# triState.net
KiCad netlist of a schematic drawn in EAGLE
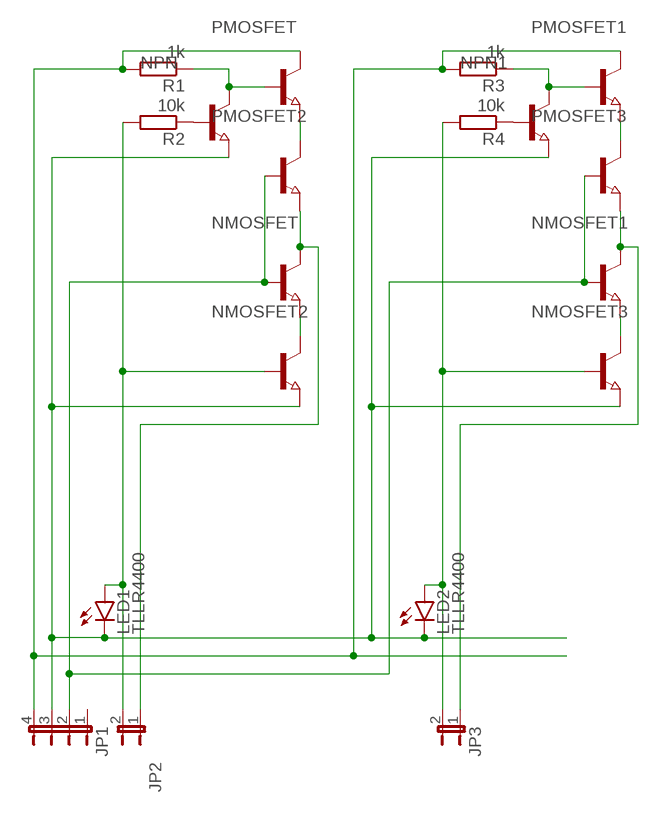
[diagram p0: schematic, sheet 1]

(export (version "E")
  (design (tool "Eeschema 10.0.6"))
  (components
    (comp (ref "JP1")
      (value "JP4E")
      (footprint "eagle-import:JP4")
      (libsource (lib "eagle-import") (part "JP4E"))
    )
    (comp (ref "JP2")
      (value "JP1E")
      (footprint "eagle-import:JP1")
      (libsource (lib "eagle-import") (part "JP1E"))
    )
    (comp (ref "JP3")
      (value "JP1E")
      (footprint "eagle-import:JP1")
      (libsource (lib "eagle-import") (part "JP1E"))
    )
    (comp (ref "LED1")
      (value "TLLR4400")
      (footprint "eagle-import:LED3MM")
      (fields (field (name "MF") "VISHAY SEMICONDUCTOR"))
      (libsource (lib "eagle-import") (part "TLLR4400"))
    )
    (comp (ref "LED2")
      (value "TLLR4400")
      (footprint "eagle-import:LED3MM")
      (fields (field (name "MF") "VISHAY SEMICONDUCTOR"))
      (libsource (lib "eagle-import") (part "TLLR4400"))
    )
    (comp (ref "NMOSFET")
      (value "NPN-TRANSISTOR_SOT23")
      (footprint "eagle-import:SOT23")
      (libsource (lib "eagle-import") (part "NPN-TRANSISTOR_SOT23"))
    )
    (comp (ref "NMOSFET1")
      (value "NPN-TRANSISTOR_SOT23")
      (footprint "eagle-import:SOT23")
      (libsource (lib "eagle-import") (part "NPN-TRANSISTOR_SOT23"))
    )
    (comp (ref "NMOSFET2")
      (value "NPN-TRANSISTOR_SOT23")
      (footprint "eagle-import:SOT23")
      (libsource (lib "eagle-import") (part "NPN-TRANSISTOR_SOT23"))
    )
    (comp (ref "NMOSFET3")
      (value "NPN-TRANSISTOR_SOT23")
      (footprint "eagle-import:SOT23")
      (libsource (lib "eagle-import") (part "NPN-TRANSISTOR_SOT23"))
    )
    (comp (ref "NPN")
      (value "NPN-TRANSISTOR_SOT23")
      (footprint "eagle-import:SOT23")
      (libsource (lib "eagle-import") (part "NPN-TRANSISTOR_SOT23"))
    )
    (comp (ref "NPN1")
      (value "NPN-TRANSISTOR_SOT23")
      (footprint "eagle-import:SOT23")
      (libsource (lib "eagle-import") (part "NPN-TRANSISTOR_SOT23"))
    )
    (comp (ref "PMOSFET")
      (value "NPN-TRANSISTOR_SOT23")
      (footprint "eagle-import:SOT23")
      (libsource (lib "eagle-import") (part "NPN-TRANSISTOR_SOT23"))
    )
    (comp (ref "PMOSFET1")
      (value "NPN-TRANSISTOR_SOT23")
      (footprint "eagle-import:SOT23")
      (libsource (lib "eagle-import") (part "NPN-TRANSISTOR_SOT23"))
    )
    (comp (ref "PMOSFET2")
      (value "NPN-TRANSISTOR_SOT23")
      (footprint "eagle-import:SOT23")
      (libsource (lib "eagle-import") (part "NPN-TRANSISTOR_SOT23"))
    )
    (comp (ref "PMOSFET3")
      (value "NPN-TRANSISTOR_SOT23")
      (footprint "eagle-import:SOT23")
      (libsource (lib "eagle-import") (part "NPN-TRANSISTOR_SOT23"))
    )
    (comp (ref "R1")
      (value "1k")
      (footprint "eagle-import:R1206")
      (libsource (lib "eagle-import") (part "R-EU_R1206"))
    )
    (comp (ref "R2")
      (value "10k")
      (footprint "eagle-import:R1206")
      (libsource (lib "eagle-import") (part "R-EU_R1206"))
    )
    (comp (ref "R3")
      (value "1k")
      (footprint "eagle-import:R1206")
      (libsource (lib "eagle-import") (part "R-EU_R1206"))
    )
    (comp (ref "R4")
      (value "10k")
      (footprint "eagle-import:R1206")
      (libsource (lib "eagle-import") (part "R-EU_R1206"))
    )
  )
  (nets
    (net (code "1") (name "Net-(LED1-C)") (class "Default")
      (node (ref "JP1") (pin "3") (pinfunction "3_3") (pintype "passive"))
      (node (ref "LED1") (pin "K") (pinfunction "C_K") (pintype "passive"))
      (node (ref "LED2") (pin "K") (pinfunction "C_K") (pintype "passive"))
      (node (ref "NMOSFET2") (pin "2") (pinfunction "E_2") (pintype "passive"))
      (node (ref "NMOSFET3") (pin "2") (pinfunction "E_2") (pintype "passive"))
      (node (ref "NPN") (pin "2") (pinfunction "E_2") (pintype "passive"))
      (node (ref "NPN1") (pin "2") (pinfunction "E_2") (pintype "passive"))
    )
    (net (code "2") (name "Net-(NMOSFET-B)") (class "Default")
      (node (ref "JP1") (pin "2") (pinfunction "2_2") (pintype "passive"))
      (node (ref "NMOSFET") (pin "1") (pinfunction "B_1") (pintype "passive"))
      (node (ref "NMOSFET1") (pin "1") (pinfunction "B_1") (pintype "passive"))
      (node (ref "PMOSFET2") (pin "1") (pinfunction "B_1") (pintype "passive"))
      (node (ref "PMOSFET3") (pin "1") (pinfunction "B_1") (pintype "passive"))
    )
    (net (code "3") (name "Net-(NMOSFET-C)") (class "Default")
      (node (ref "JP2") (pin "1") (pinfunction "1_1") (pintype "passive"))
      (node (ref "NMOSFET") (pin "3") (pinfunction "C_3") (pintype "passive"))
      (node (ref "PMOSFET2") (pin "2") (pinfunction "E_2") (pintype "passive"))
    )
    (net (code "4") (name "Net-(NMOSFET-E)") (class "Default")
      (node (ref "NMOSFET") (pin "2") (pinfunction "E_2") (pintype "passive"))
      (node (ref "NMOSFET2") (pin "3") (pinfunction "C_3") (pintype "passive"))
    )
    (net (code "5") (name "Net-(NMOSFET1-C)") (class "Default")
      (node (ref "JP3") (pin "1") (pinfunction "1_1") (pintype "passive"))
      (node (ref "NMOSFET1") (pin "3") (pinfunction "C_3") (pintype "passive"))
      (node (ref "PMOSFET3") (pin "2") (pinfunction "E_2") (pintype "passive"))
    )
    (net (code "6") (name "Net-(NMOSFET1-E)") (class "Default")
      (node (ref "NMOSFET1") (pin "2") (pinfunction "E_2") (pintype "passive"))
      (node (ref "NMOSFET3") (pin "3") (pinfunction "C_3") (pintype "passive"))
    )
    (net (code "7") (name "Net-(NMOSFET2-B)") (class "Default")
      (node (ref "JP2") (pin "2") (pinfunction "2_2") (pintype "passive"))
      (node (ref "LED1") (pin "A") (pinfunction "A_A") (pintype "passive"))
      (node (ref "NMOSFET2") (pin "1") (pinfunction "B_1") (pintype "passive"))
      (node (ref "R2") (pin "2") (pinfunction "2_2") (pintype "passive"))
    )
    (net (code "8") (name "Net-(NMOSFET3-B)") (class "Default")
      (node (ref "JP3") (pin "2") (pinfunction "2_2") (pintype "passive"))
      (node (ref "LED2") (pin "A") (pinfunction "A_A") (pintype "passive"))
      (node (ref "NMOSFET3") (pin "1") (pinfunction "B_1") (pintype "passive"))
      (node (ref "R4") (pin "2") (pinfunction "2_2") (pintype "passive"))
    )
    (net (code "9") (name "Net-(NPN-B)") (class "Default")
      (node (ref "NPN") (pin "1") (pinfunction "B_1") (pintype "passive"))
      (node (ref "R2") (pin "1") (pinfunction "1_1") (pintype "passive"))
    )
    (net (code "10") (name "Net-(NPN-C)") (class "Default")
      (node (ref "NPN") (pin "3") (pinfunction "C_3") (pintype "passive"))
      (node (ref "PMOSFET") (pin "1") (pinfunction "B_1") (pintype "passive"))
      (node (ref "R1") (pin "1") (pinfunction "1_1") (pintype "passive"))
    )
    (net (code "11") (name "Net-(NPN1-B)") (class "Default")
      (node (ref "NPN1") (pin "1") (pinfunction "B_1") (pintype "passive"))
      (node (ref "R4") (pin "1") (pinfunction "1_1") (pintype "passive"))
    )
    (net (code "12") (name "Net-(NPN1-C)") (class "Default")
      (node (ref "NPN1") (pin "3") (pinfunction "C_3") (pintype "passive"))
      (node (ref "PMOSFET1") (pin "1") (pinfunction "B_1") (pintype "passive"))
      (node (ref "R3") (pin "1") (pinfunction "1_1") (pintype "passive"))
    )
    (net (code "13") (name "Net-(PMOSFET-C)") (class "Default")
      (node (ref "JP1") (pin "4") (pinfunction "4_4") (pintype "passive"))
      (node (ref "PMOSFET") (pin "3") (pinfunction "C_3") (pintype "passive"))
      (node (ref "PMOSFET1") (pin "3") (pinfunction "C_3") (pintype "passive"))
      (node (ref "R1") (pin "2") (pinfunction "2_2") (pintype "passive"))
      (node (ref "R3") (pin "2") (pinfunction "2_2") (pintype "passive"))
    )
    (net (code "14") (name "Net-(PMOSFET-E)") (class "Default")
      (node (ref "PMOSFET") (pin "2") (pinfunction "E_2") (pintype "passive"))
      (node (ref "PMOSFET2") (pin "3") (pinfunction "C_3") (pintype "passive"))
    )
    (net (code "15") (name "Net-(PMOSFET1-E)") (class "Default")
      (node (ref "PMOSFET1") (pin "2") (pinfunction "E_2") (pintype "passive"))
      (node (ref "PMOSFET3") (pin "3") (pinfunction "C_3") (pintype "passive"))
    )
    (net (code "16") (name "unconnected-(JP1-Pad1)") (class "Default")
      (node (ref "JP1") (pin "1") (pinfunction "1_1") (pintype "passive"))
    )
  )
)
